# Peripherals.net
KiCad netlist of a schematic drawn in Altium Designer
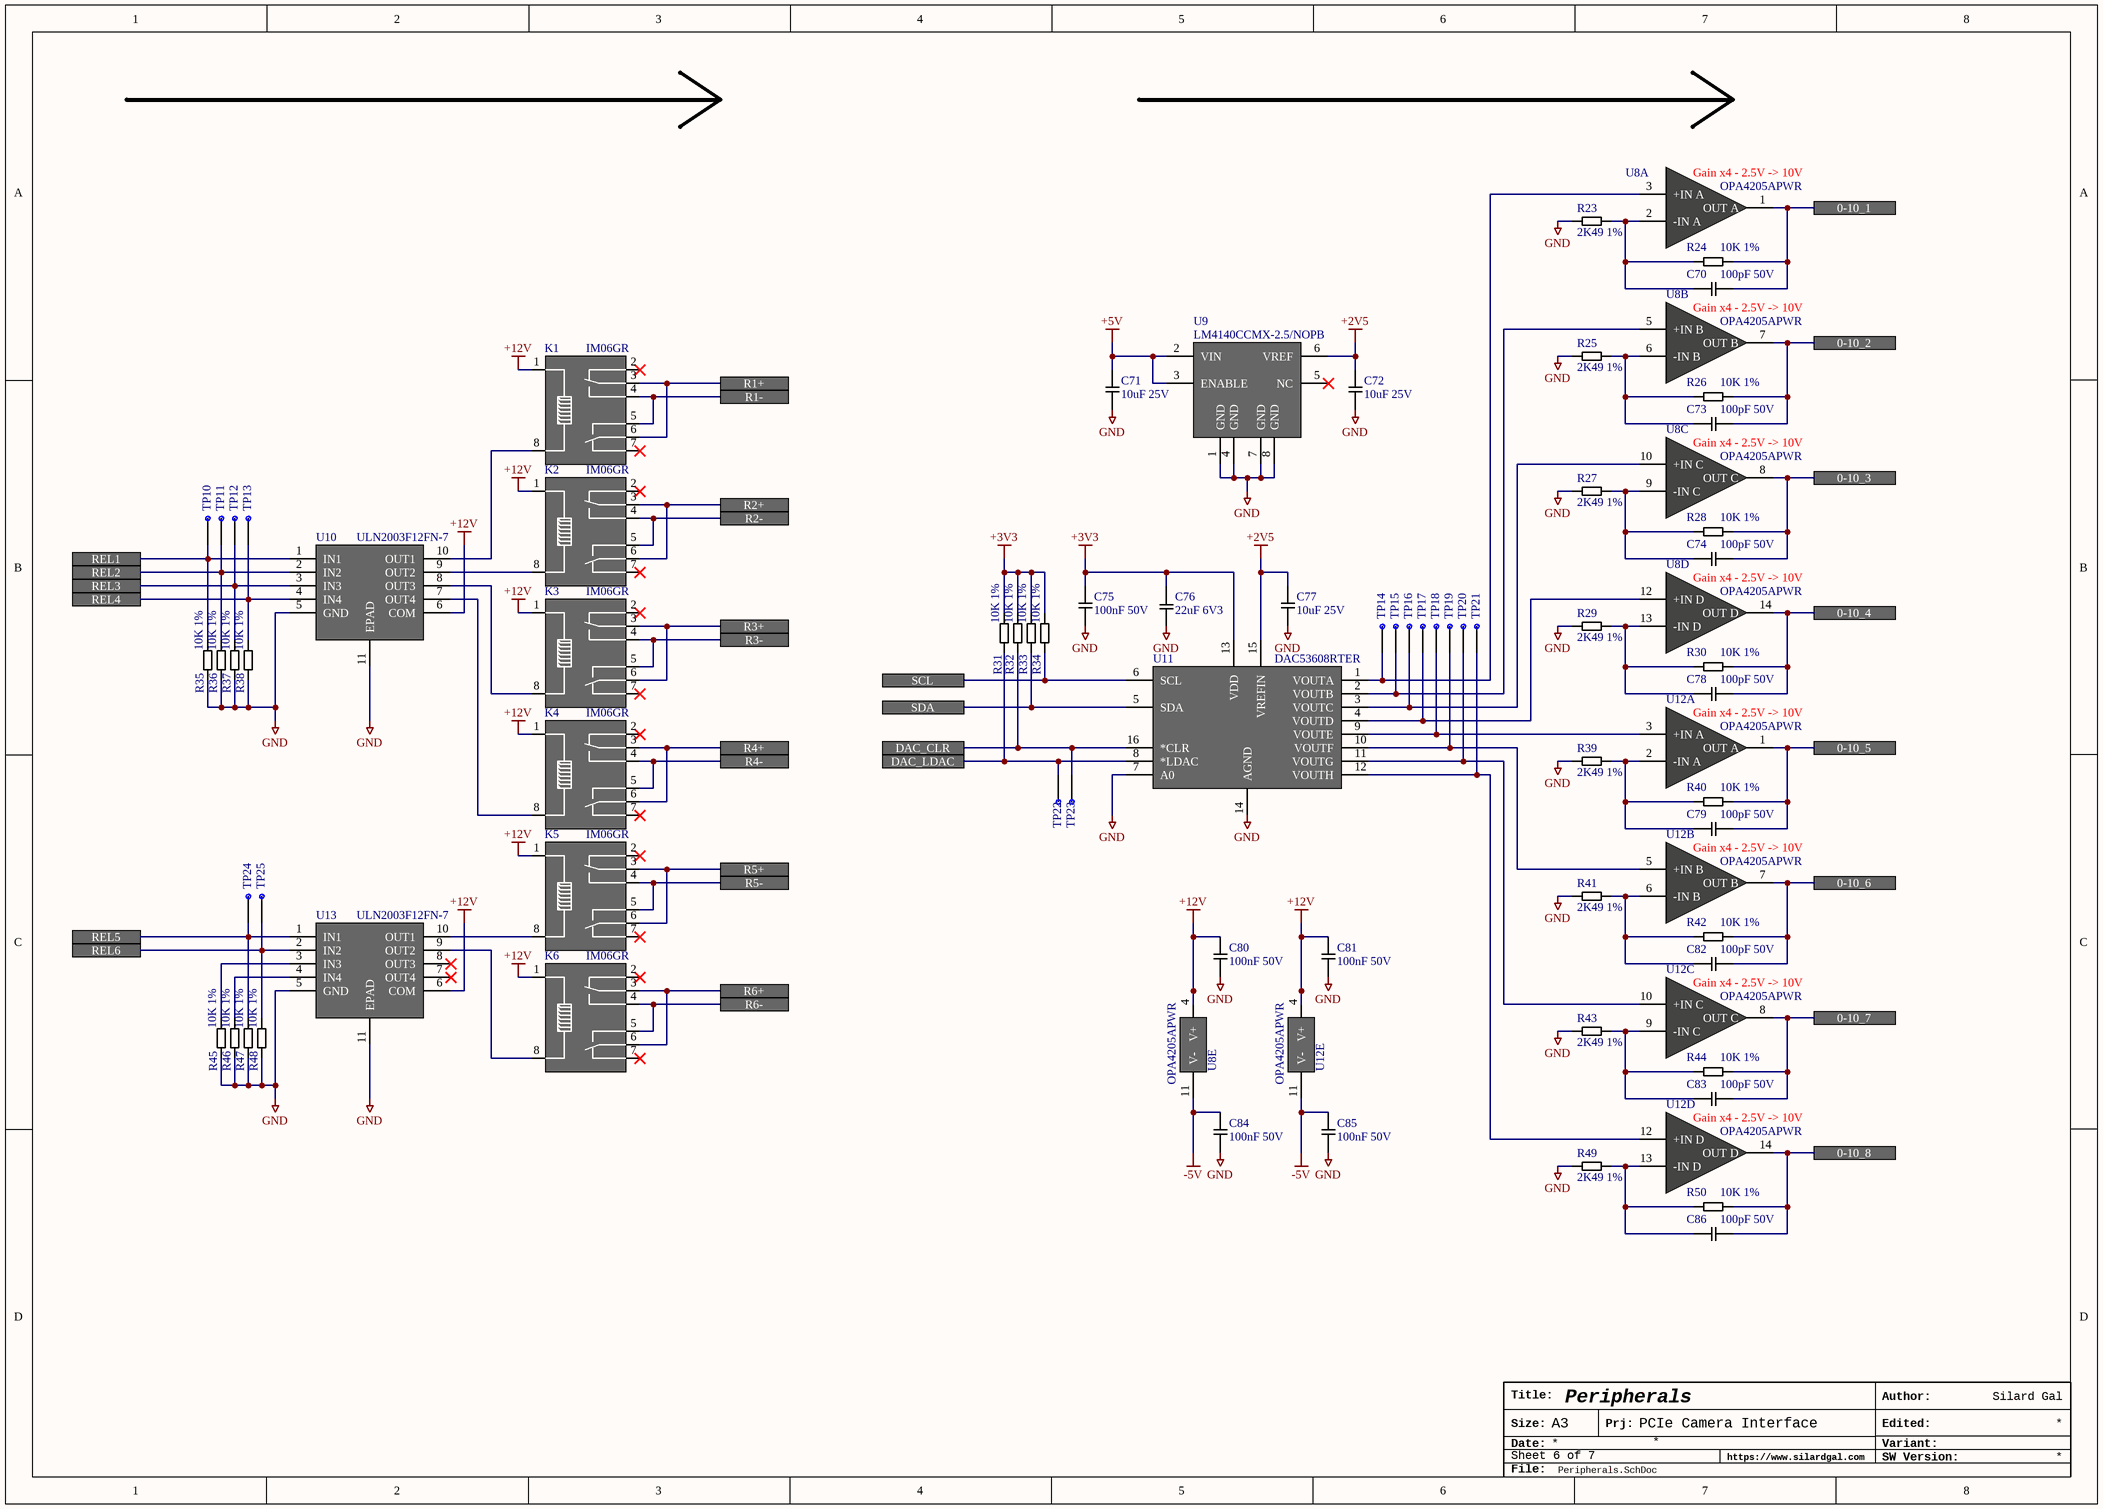
[diagram p0: Peripherals.SchDoc]

(export (version "E")
  (design (tool "Eeschema 10.0.6"))
  (components
    (comp (ref "C70")
      (value "100pF 50V")
      (footprint "CAPC1608X06N")
      (description "100 pF ±10% 50V Ceramic Capacitor C0G, NP0 0603 (1608 Metric)")
      (fields (field (name "MPN") "KGM15ACG1H101KT"))
      (libsource (lib "PCIe_Camera_Interface_Library") (part "100pF 50V"))
    )
    (comp (ref "C71")
      (value "10uF 25V")
      (footprint "CAPC1608X06N")
      (description "10 µF ±20% 25V Ceramic Capacitor X5R 0603 (1608 Metric)")
      (fields (field (name "MPN") "GRM188R61E106MA73D"))
      (libsource (lib "PCIe_Camera_Interface_Library") (part "10uF 25V"))
    )
    (comp (ref "C72")
      (value "10uF 25V")
      (footprint "CAPC1608X06N")
      (description "10 µF ±20% 25V Ceramic Capacitor X5R 0603 (1608 Metric)")
      (fields (field (name "MPN") "GRM188R61E106MA73D"))
      (libsource (lib "PCIe_Camera_Interface_Library") (part "10uF 25V"))
    )
    (comp (ref "C73")
      (value "100pF 50V")
      (footprint "CAPC1608X06N")
      (description "100 pF ±10% 50V Ceramic Capacitor C0G, NP0 0603 (1608 Metric)")
      (fields (field (name "MPN") "KGM15ACG1H101KT"))
      (libsource (lib "PCIe_Camera_Interface_Library") (part "100pF 50V"))
    )
    (comp (ref "C74")
      (value "100pF 50V")
      (footprint "CAPC1608X06N")
      (description "100 pF ±10% 50V Ceramic Capacitor C0G, NP0 0603 (1608 Metric)")
      (fields (field (name "MPN") "KGM15ACG1H101KT"))
      (libsource (lib "PCIe_Camera_Interface_Library") (part "100pF 50V"))
    )
    (comp (ref "C75")
      (value "100nF 50V")
      (footprint "CAPC1608X06N")
      (description "0.1 µF ±10% 50V Ceramic Capacitor X7R 0603 (1608 Metric)")
      (fields (field (name "MPN") "GCM188R71H104KA57D"))
      (libsource (lib "PCIe_Camera_Interface_Library") (part "100nF 50V"))
    )
    (comp (ref "C76")
      (value "22uF 6V3")
      (footprint "CAPC1608X06N")
      (description "22 µF ±20% 6.3V Ceramic Capacitor X5R 0603 (1608 Metric)")
      (fields (field (name "MPN") "GRM188R60J226MEA0D"))
      (libsource (lib "PCIe_Camera_Interface_Library") (part "22uF 6V3"))
    )
    (comp (ref "C77")
      (value "10uF 25V")
      (footprint "CAPC1608X06N")
      (description "10 µF ±20% 25V Ceramic Capacitor X5R 0603 (1608 Metric)")
      (fields (field (name "MPN") "GRM188R61E106MA73D"))
      (libsource (lib "PCIe_Camera_Interface_Library") (part "10uF 25V"))
    )
    (comp (ref "C78")
      (value "100pF 50V")
      (footprint "CAPC1608X06N")
      (description "100 pF ±10% 50V Ceramic Capacitor C0G, NP0 0603 (1608 Metric)")
      (fields (field (name "MPN") "KGM15ACG1H101KT"))
      (libsource (lib "PCIe_Camera_Interface_Library") (part "100pF 50V"))
    )
    (comp (ref "C79")
      (value "100pF 50V")
      (footprint "CAPC1608X06N")
      (description "100 pF ±10% 50V Ceramic Capacitor C0G, NP0 0603 (1608 Metric)")
      (fields (field (name "MPN") "KGM15ACG1H101KT"))
      (libsource (lib "PCIe_Camera_Interface_Library") (part "100pF 50V"))
    )
    (comp (ref "C80")
      (value "100nF 50V")
      (footprint "CAPC1608X06N")
      (description "0.1 µF ±10% 50V Ceramic Capacitor X7R 0603 (1608 Metric)")
      (fields (field (name "MPN") "GCM188R71H104KA57D"))
      (libsource (lib "PCIe_Camera_Interface_Library") (part "100nF 50V"))
    )
    (comp (ref "C81")
      (value "100nF 50V")
      (footprint "CAPC1608X06N")
      (description "0.1 µF ±10% 50V Ceramic Capacitor X7R 0603 (1608 Metric)")
      (fields (field (name "MPN") "GCM188R71H104KA57D"))
      (libsource (lib "PCIe_Camera_Interface_Library") (part "100nF 50V"))
    )
    (comp (ref "C82")
      (value "100pF 50V")
      (footprint "CAPC1608X06N")
      (description "100 pF ±10% 50V Ceramic Capacitor C0G, NP0 0603 (1608 Metric)")
      (fields (field (name "MPN") "KGM15ACG1H101KT"))
      (libsource (lib "PCIe_Camera_Interface_Library") (part "100pF 50V"))
    )
    (comp (ref "C83")
      (value "100pF 50V")
      (footprint "CAPC1608X06N")
      (description "100 pF ±10% 50V Ceramic Capacitor C0G, NP0 0603 (1608 Metric)")
      (fields (field (name "MPN") "KGM15ACG1H101KT"))
      (libsource (lib "PCIe_Camera_Interface_Library") (part "100pF 50V"))
    )
    (comp (ref "C84")
      (value "100nF 50V")
      (footprint "CAPC1608X06N")
      (description "0.1 µF ±10% 50V Ceramic Capacitor X7R 0603 (1608 Metric)")
      (fields (field (name "MPN") "GCM188R71H104KA57D"))
      (libsource (lib "PCIe_Camera_Interface_Library") (part "100nF 50V"))
    )
    (comp (ref "C85")
      (value "100nF 50V")
      (footprint "CAPC1608X06N")
      (description "0.1 µF ±10% 50V Ceramic Capacitor X7R 0603 (1608 Metric)")
      (fields (field (name "MPN") "GCM188R71H104KA57D"))
      (libsource (lib "PCIe_Camera_Interface_Library") (part "100nF 50V"))
    )
    (comp (ref "C86")
      (value "100pF 50V")
      (footprint "CAPC1608X06N")
      (description "100 pF ±10% 50V Ceramic Capacitor C0G, NP0 0603 (1608 Metric)")
      (fields (field (name "MPN") "KGM15ACG1H101KT"))
      (libsource (lib "PCIe_Camera_Interface_Library") (part "100pF 50V"))
    )
    (comp (ref "K1")
      (value "IM06GR")
      (footprint "IM06GR")
      (description "Telecom Relay DPDT (2 Form C) Surface Mount")
      (libsource (lib "PCIe_Camera_Interface_Library") (part "IM06GR"))
    )
    (comp (ref "K2")
      (value "IM06GR")
      (footprint "IM06GR")
      (description "Telecom Relay DPDT (2 Form C) Surface Mount")
      (libsource (lib "PCIe_Camera_Interface_Library") (part "IM06GR"))
    )
    (comp (ref "K3")
      (value "IM06GR")
      (footprint "IM06GR")
      (description "Telecom Relay DPDT (2 Form C) Surface Mount")
      (libsource (lib "PCIe_Camera_Interface_Library") (part "IM06GR"))
    )
    (comp (ref "K4")
      (value "IM06GR")
      (footprint "IM06GR")
      (description "Telecom Relay DPDT (2 Form C) Surface Mount")
      (libsource (lib "PCIe_Camera_Interface_Library") (part "IM06GR"))
    )
    (comp (ref "K5")
      (value "IM06GR")
      (footprint "IM06GR")
      (description "Telecom Relay DPDT (2 Form C) Surface Mount")
      (libsource (lib "PCIe_Camera_Interface_Library") (part "IM06GR"))
    )
    (comp (ref "K6")
      (value "IM06GR")
      (footprint "IM06GR")
      (description "Telecom Relay DPDT (2 Form C) Surface Mount")
      (libsource (lib "PCIe_Camera_Interface_Library") (part "IM06GR"))
    )
    (comp (ref "R23")
      (value "2K49 1%")
      (footprint "RESC1608X06N")
      (description "2.49 kOhms ±1% 0.1W, 1/10W Chip Resistor 0603 (1608 Metric) Automotive AEC-Q200 Thick Film")
      (fields (field (name "MPN") "RMCF0603FT2K49"))
      (libsource (lib "PCIe_Camera_Interface_Library") (part "2K49 1%"))
    )
    (comp (ref "R24")
      (value "10K 1%")
      (footprint "RESC1608X06N")
      (description "10 kOhms ±1% 0.1W, 1/10W Chip Resistor 0603 (1608 Metric) Automotive AEC-Q200 Thick Film")
      (fields (field (name "MPN") "ERJ-3EKF1002V"))
      (libsource (lib "PCIe_Camera_Interface_Library") (part "10K 1%"))
    )
    (comp (ref "R25")
      (value "2K49 1%")
      (footprint "RESC1608X06N")
      (description "2.49 kOhms ±1% 0.1W, 1/10W Chip Resistor 0603 (1608 Metric) Automotive AEC-Q200 Thick Film")
      (fields (field (name "MPN") "RMCF0603FT2K49"))
      (libsource (lib "PCIe_Camera_Interface_Library") (part "2K49 1%"))
    )
    (comp (ref "R26")
      (value "10K 1%")
      (footprint "RESC1608X06N")
      (description "10 kOhms ±1% 0.1W, 1/10W Chip Resistor 0603 (1608 Metric) Automotive AEC-Q200 Thick Film")
      (fields (field (name "MPN") "ERJ-3EKF1002V"))
      (libsource (lib "PCIe_Camera_Interface_Library") (part "10K 1%"))
    )
    (comp (ref "R27")
      (value "2K49 1%")
      (footprint "RESC1608X06N")
      (description "2.49 kOhms ±1% 0.1W, 1/10W Chip Resistor 0603 (1608 Metric) Automotive AEC-Q200 Thick Film")
      (fields (field (name "MPN") "RMCF0603FT2K49"))
      (libsource (lib "PCIe_Camera_Interface_Library") (part "2K49 1%"))
    )
    (comp (ref "R28")
      (value "10K 1%")
      (footprint "RESC1608X06N")
      (description "10 kOhms ±1% 0.1W, 1/10W Chip Resistor 0603 (1608 Metric) Automotive AEC-Q200 Thick Film")
      (fields (field (name "MPN") "ERJ-3EKF1002V"))
      (libsource (lib "PCIe_Camera_Interface_Library") (part "10K 1%"))
    )
    (comp (ref "R29")
      (value "2K49 1%")
      (footprint "RESC1608X06N")
      (description "2.49 kOhms ±1% 0.1W, 1/10W Chip Resistor 0603 (1608 Metric) Automotive AEC-Q200 Thick Film")
      (fields (field (name "MPN") "RMCF0603FT2K49"))
      (libsource (lib "PCIe_Camera_Interface_Library") (part "2K49 1%"))
    )
    (comp (ref "R30")
      (value "10K 1%")
      (footprint "RESC1608X06N")
      (description "10 kOhms ±1% 0.1W, 1/10W Chip Resistor 0603 (1608 Metric) Automotive AEC-Q200 Thick Film")
      (fields (field (name "MPN") "ERJ-3EKF1002V"))
      (libsource (lib "PCIe_Camera_Interface_Library") (part "10K 1%"))
    )
    (comp (ref "R31")
      (value "10K 1%")
      (footprint "RESC1608X06N")
      (description "10 kOhms ±1% 0.1W, 1/10W Chip Resistor 0603 (1608 Metric) Automotive AEC-Q200 Thick Film")
      (fields (field (name "MPN") "ERJ-3EKF1002V"))
      (libsource (lib "PCIe_Camera_Interface_Library") (part "10K 1%"))
    )
    (comp (ref "R32")
      (value "10K 1%")
      (footprint "RESC1608X06N")
      (description "10 kOhms ±1% 0.1W, 1/10W Chip Resistor 0603 (1608 Metric) Automotive AEC-Q200 Thick Film")
      (fields (field (name "MPN") "ERJ-3EKF1002V"))
      (libsource (lib "PCIe_Camera_Interface_Library") (part "10K 1%"))
    )
    (comp (ref "R33")
      (value "10K 1%")
      (footprint "RESC1608X06N")
      (description "10 kOhms ±1% 0.1W, 1/10W Chip Resistor 0603 (1608 Metric) Automotive AEC-Q200 Thick Film")
      (fields (field (name "MPN") "ERJ-3EKF1002V"))
      (libsource (lib "PCIe_Camera_Interface_Library") (part "10K 1%"))
    )
    (comp (ref "R34")
      (value "10K 1%")
      (footprint "RESC1608X06N")
      (description "10 kOhms ±1% 0.1W, 1/10W Chip Resistor 0603 (1608 Metric) Automotive AEC-Q200 Thick Film")
      (fields (field (name "MPN") "ERJ-3EKF1002V"))
      (libsource (lib "PCIe_Camera_Interface_Library") (part "10K 1%"))
    )
    (comp (ref "R35")
      (value "10K 1%")
      (footprint "RESC1608X06N")
      (description "10 kOhms ±1% 0.1W, 1/10W Chip Resistor 0603 (1608 Metric) Automotive AEC-Q200 Thick Film")
      (fields (field (name "MPN") "ERJ-3EKF1002V"))
      (libsource (lib "PCIe_Camera_Interface_Library") (part "10K 1%"))
    )
    (comp (ref "R36")
      (value "10K 1%")
      (footprint "RESC1608X06N")
      (description "10 kOhms ±1% 0.1W, 1/10W Chip Resistor 0603 (1608 Metric) Automotive AEC-Q200 Thick Film")
      (fields (field (name "MPN") "ERJ-3EKF1002V"))
      (libsource (lib "PCIe_Camera_Interface_Library") (part "10K 1%"))
    )
    (comp (ref "R37")
      (value "10K 1%")
      (footprint "RESC1608X06N")
      (description "10 kOhms ±1% 0.1W, 1/10W Chip Resistor 0603 (1608 Metric) Automotive AEC-Q200 Thick Film")
      (fields (field (name "MPN") "ERJ-3EKF1002V"))
      (libsource (lib "PCIe_Camera_Interface_Library") (part "10K 1%"))
    )
    (comp (ref "R38")
      (value "10K 1%")
      (footprint "RESC1608X06N")
      (description "10 kOhms ±1% 0.1W, 1/10W Chip Resistor 0603 (1608 Metric) Automotive AEC-Q200 Thick Film")
      (fields (field (name "MPN") "ERJ-3EKF1002V"))
      (libsource (lib "PCIe_Camera_Interface_Library") (part "10K 1%"))
    )
    (comp (ref "R39")
      (value "2K49 1%")
      (footprint "RESC1608X06N")
      (description "2.49 kOhms ±1% 0.1W, 1/10W Chip Resistor 0603 (1608 Metric) Automotive AEC-Q200 Thick Film")
      (fields (field (name "MPN") "RMCF0603FT2K49"))
      (libsource (lib "PCIe_Camera_Interface_Library") (part "2K49 1%"))
    )
    (comp (ref "R40")
      (value "10K 1%")
      (footprint "RESC1608X06N")
      (description "10 kOhms ±1% 0.1W, 1/10W Chip Resistor 0603 (1608 Metric) Automotive AEC-Q200 Thick Film")
      (fields (field (name "MPN") "ERJ-3EKF1002V"))
      (libsource (lib "PCIe_Camera_Interface_Library") (part "10K 1%"))
    )
    (comp (ref "R41")
      (value "2K49 1%")
      (footprint "RESC1608X06N")
      (description "2.49 kOhms ±1% 0.1W, 1/10W Chip Resistor 0603 (1608 Metric) Automotive AEC-Q200 Thick Film")
      (fields (field (name "MPN") "RMCF0603FT2K49"))
      (libsource (lib "PCIe_Camera_Interface_Library") (part "2K49 1%"))
    )
    (comp (ref "R42")
      (value "10K 1%")
      (footprint "RESC1608X06N")
      (description "10 kOhms ±1% 0.1W, 1/10W Chip Resistor 0603 (1608 Metric) Automotive AEC-Q200 Thick Film")
      (fields (field (name "MPN") "ERJ-3EKF1002V"))
      (libsource (lib "PCIe_Camera_Interface_Library") (part "10K 1%"))
    )
    (comp (ref "R43")
      (value "2K49 1%")
      (footprint "RESC1608X06N")
      (description "2.49 kOhms ±1% 0.1W, 1/10W Chip Resistor 0603 (1608 Metric) Automotive AEC-Q200 Thick Film")
      (fields (field (name "MPN") "RMCF0603FT2K49"))
      (libsource (lib "PCIe_Camera_Interface_Library") (part "2K49 1%"))
    )
    (comp (ref "R44")
      (value "10K 1%")
      (footprint "RESC1608X06N")
      (description "10 kOhms ±1% 0.1W, 1/10W Chip Resistor 0603 (1608 Metric) Automotive AEC-Q200 Thick Film")
      (fields (field (name "MPN") "ERJ-3EKF1002V"))
      (libsource (lib "PCIe_Camera_Interface_Library") (part "10K 1%"))
    )
    (comp (ref "R45")
      (value "10K 1%")
      (footprint "RESC1608X06N")
      (description "10 kOhms ±1% 0.1W, 1/10W Chip Resistor 0603 (1608 Metric) Automotive AEC-Q200 Thick Film")
      (fields (field (name "MPN") "ERJ-3EKF1002V"))
      (libsource (lib "PCIe_Camera_Interface_Library") (part "10K 1%"))
    )
    (comp (ref "R46")
      (value "10K 1%")
      (footprint "RESC1608X06N")
      (description "10 kOhms ±1% 0.1W, 1/10W Chip Resistor 0603 (1608 Metric) Automotive AEC-Q200 Thick Film")
      (fields (field (name "MPN") "ERJ-3EKF1002V"))
      (libsource (lib "PCIe_Camera_Interface_Library") (part "10K 1%"))
    )
    (comp (ref "R47")
      (value "10K 1%")
      (footprint "RESC1608X06N")
      (description "10 kOhms ±1% 0.1W, 1/10W Chip Resistor 0603 (1608 Metric) Automotive AEC-Q200 Thick Film")
      (fields (field (name "MPN") "ERJ-3EKF1002V"))
      (libsource (lib "PCIe_Camera_Interface_Library") (part "10K 1%"))
    )
    (comp (ref "R48")
      (value "10K 1%")
      (footprint "RESC1608X06N")
      (description "10 kOhms ±1% 0.1W, 1/10W Chip Resistor 0603 (1608 Metric) Automotive AEC-Q200 Thick Film")
      (fields (field (name "MPN") "ERJ-3EKF1002V"))
      (libsource (lib "PCIe_Camera_Interface_Library") (part "10K 1%"))
    )
    (comp (ref "R49")
      (value "2K49 1%")
      (footprint "RESC1608X06N")
      (description "2.49 kOhms ±1% 0.1W, 1/10W Chip Resistor 0603 (1608 Metric) Automotive AEC-Q200 Thick Film")
      (fields (field (name "MPN") "RMCF0603FT2K49"))
      (libsource (lib "PCIe_Camera_Interface_Library") (part "2K49 1%"))
    )
    (comp (ref "R50")
      (value "10K 1%")
      (footprint "RESC1608X06N")
      (description "10 kOhms ±1% 0.1W, 1/10W Chip Resistor 0603 (1608 Metric) Automotive AEC-Q200 Thick Film")
      (fields (field (name "MPN") "ERJ-3EKF1002V"))
      (libsource (lib "PCIe_Camera_Interface_Library") (part "10K 1%"))
    )
    (comp (ref "TP10")
      (value "TP")
      (footprint "TP")
      (libsource (lib "PCIe_Camera_Interface_Library") (part "TP"))
    )
    (comp (ref "TP11")
      (value "TP")
      (footprint "TP")
      (libsource (lib "PCIe_Camera_Interface_Library") (part "TP"))
    )
    (comp (ref "TP12")
      (value "TP")
      (footprint "TP")
      (libsource (lib "PCIe_Camera_Interface_Library") (part "TP"))
    )
    (comp (ref "TP13")
      (value "TP")
      (footprint "TP")
      (libsource (lib "PCIe_Camera_Interface_Library") (part "TP"))
    )
    (comp (ref "TP14")
      (value "TP")
      (footprint "TP")
      (libsource (lib "PCIe_Camera_Interface_Library") (part "TP"))
    )
    (comp (ref "TP15")
      (value "TP")
      (footprint "TP")
      (libsource (lib "PCIe_Camera_Interface_Library") (part "TP"))
    )
    (comp (ref "TP16")
      (value "TP")
      (footprint "TP")
      (libsource (lib "PCIe_Camera_Interface_Library") (part "TP"))
    )
    (comp (ref "TP17")
      (value "TP")
      (footprint "TP")
      (libsource (lib "PCIe_Camera_Interface_Library") (part "TP"))
    )
    (comp (ref "TP18")
      (value "TP")
      (footprint "TP")
      (libsource (lib "PCIe_Camera_Interface_Library") (part "TP"))
    )
    (comp (ref "TP19")
      (value "TP")
      (footprint "TP")
      (libsource (lib "PCIe_Camera_Interface_Library") (part "TP"))
    )
    (comp (ref "TP20")
      (value "TP")
      (footprint "TP")
      (libsource (lib "PCIe_Camera_Interface_Library") (part "TP"))
    )
    (comp (ref "TP21")
      (value "TP")
      (footprint "TP")
      (libsource (lib "PCIe_Camera_Interface_Library") (part "TP"))
    )
    (comp (ref "TP22")
      (value "TP")
      (footprint "TP")
      (libsource (lib "PCIe_Camera_Interface_Library") (part "TP"))
    )
    (comp (ref "TP23")
      (value "TP")
      (footprint "TP")
      (libsource (lib "PCIe_Camera_Interface_Library") (part "TP"))
    )
    (comp (ref "TP24")
      (value "TP")
      (footprint "TP")
      (libsource (lib "PCIe_Camera_Interface_Library") (part "TP"))
    )
    (comp (ref "TP25")
      (value "TP")
      (footprint "TP")
      (libsource (lib "PCIe_Camera_Interface_Library") (part "TP"))
    )
    (comp (ref "U8")
      (value "OPA4205APWR")
      (footprint "TSSO14P440")
      (description "General Purpose Amplifier 4 Circuit Push-Pull, Rail-to-Rail 14-TSSOP")
      (libsource (lib "PCIe_Camera_Interface_Library") (part "OPA4205APWR"))
    )
    (comp (ref "U9")
      (value "LM4140CCMX-2.5/NOPB")
      (footprint "SOIC127P599X175-8N")
      (description "Series Voltage Reference IC Fixed 2.5V V ±0.1% 8 mA 8-SOIC")
      (libsource (lib "PCIe_Camera_Interface_Library") (part "LM4140CCMX-2.5/NOPB"))
    )
    (comp (ref "U10")
      (value "ULN2003F12FN-7")
      (footprint "DFN3030")
      (description "Power Switch/Driver 1:1 Darlington 700mA U-DFN3030-10")
      (libsource (lib "PCIe_Camera_Interface_Library") (part "ULN2003F12FN-7"))
    )
    (comp (ref "U11")
      (value "DAC53608RTER")
      (footprint "QFN16P300X300")
      (description "10 Bit Digital to Analog Converter 8 16-WQFN (3x3)")
      (libsource (lib "PCIe_Camera_Interface_Library") (part "DAC53608RTER"))
    )
    (comp (ref "U12")
      (value "OPA4205APWR")
      (footprint "TSSO14P440")
      (description "General Purpose Amplifier 4 Circuit Push-Pull, Rail-to-Rail 14-TSSOP")
      (libsource (lib "PCIe_Camera_Interface_Library") (part "OPA4205APWR"))
    )
    (comp (ref "U13")
      (value "ULN2003F12FN-7")
      (footprint "DFN3030")
      (description "Power Switch/Driver 1:1 Darlington 700mA U-DFN3030-10")
      (libsource (lib "PCIe_Camera_Interface_Library") (part "ULN2003F12FN-7"))
    )
  )
  (nets
    (net (code "1") (name "+2V5") (class "Default")
      (node (ref "C72") (pin "2") (pinfunction "2_2") (pintype "passive"))
      (node (ref "C77") (pin "2") (pinfunction "2_2") (pintype "passive"))
      (node (ref "U11") (pin "15") (pinfunction "VREFIN_15") (pintype "passive"))
      (node (ref "U9") (pin "6") (pinfunction "VREF_6") (pintype "passive"))
    )
    (net (code "2") (name "+3V3") (class "Default")
      (node (ref "C75") (pin "2") (pinfunction "2_2") (pintype "passive"))
      (node (ref "C76") (pin "1") (pinfunction "1_1") (pintype "passive"))
      (node (ref "R31") (pin "1") (pinfunction "1_1") (pintype "passive"))
      (node (ref "R32") (pin "1") (pinfunction "1_1") (pintype "passive"))
      (node (ref "R33") (pin "1") (pinfunction "1_1") (pintype "passive"))
      (node (ref "R34") (pin "1") (pinfunction "1_1") (pintype "passive"))
      (node (ref "U11") (pin "13") (pinfunction "VDD_13") (pintype "passive"))
    )
    (net (code "3") (name "+5V") (class "Default")
      (node (ref "C71") (pin "2") (pinfunction "2_2") (pintype "passive"))
      (node (ref "U9") (pin "2") (pinfunction "VIN_2") (pintype "passive"))
      (node (ref "U9") (pin "3") (pinfunction "ENABLE_3") (pintype "passive"))
    )
    (net (code "4") (name "+12V") (class "Default")
      (node (ref "C80") (pin "2") (pinfunction "2_2") (pintype "passive"))
      (node (ref "C81") (pin "2") (pinfunction "2_2") (pintype "passive"))
      (node (ref "K1") (pin "1") (pinfunction "1_1") (pintype "passive"))
      (node (ref "K2") (pin "1") (pinfunction "1_1") (pintype "passive"))
      (node (ref "K3") (pin "1") (pinfunction "1_1") (pintype "passive"))
      (node (ref "K4") (pin "1") (pinfunction "1_1") (pintype "passive"))
      (node (ref "K5") (pin "1") (pinfunction "1_1") (pintype "passive"))
      (node (ref "K6") (pin "1") (pinfunction "1_1") (pintype "passive"))
      (node (ref "U10") (pin "6") (pinfunction "COM_6") (pintype "passive"))
      (node (ref "U12") (pin "4") (pinfunction "V+_4") (pintype "power_in"))
      (node (ref "U13") (pin "6") (pinfunction "COM_6") (pintype "passive"))
      (node (ref "U8") (pin "4") (pinfunction "V+_4") (pintype "power_in"))
    )
    (net (code "5") (name "-5V") (class "Default")
      (node (ref "C84") (pin "2") (pinfunction "2_2") (pintype "passive"))
      (node (ref "C85") (pin "2") (pinfunction "2_2") (pintype "passive"))
      (node (ref "U12") (pin "11") (pinfunction "V-_11") (pintype "power_in"))
      (node (ref "U8") (pin "11") (pinfunction "V-_11") (pintype "power_in"))
    )
    (net (code "6") (name "/0-10_1") (class "Default")
      (node (ref "C70") (pin "2") (pinfunction "2_2") (pintype "passive"))
      (node (ref "R24") (pin "2") (pinfunction "2_2") (pintype "passive"))
      (node (ref "U8") (pin "1") (pinfunction "OUT_A_1") (pintype "passive"))
    )
    (net (code "7") (name "/0-10_2") (class "Default")
      (node (ref "C73") (pin "2") (pinfunction "2_2") (pintype "passive"))
      (node (ref "R26") (pin "2") (pinfunction "2_2") (pintype "passive"))
      (node (ref "U8") (pin "7") (pinfunction "OUT_B_7") (pintype "passive"))
    )
    (net (code "8") (name "/0-10_3") (class "Default")
      (node (ref "C74") (pin "2") (pinfunction "2_2") (pintype "passive"))
      (node (ref "R28") (pin "2") (pinfunction "2_2") (pintype "passive"))
      (node (ref "U8") (pin "8") (pinfunction "OUT_C_8") (pintype "passive"))
    )
    (net (code "9") (name "/0-10_4") (class "Default")
      (node (ref "C78") (pin "2") (pinfunction "2_2") (pintype "passive"))
      (node (ref "R30") (pin "2") (pinfunction "2_2") (pintype "passive"))
      (node (ref "U8") (pin "14") (pinfunction "OUT_D_14") (pintype "passive"))
    )
    (net (code "10") (name "/0-10_5") (class "Default")
      (node (ref "C79") (pin "2") (pinfunction "2_2") (pintype "passive"))
      (node (ref "R40") (pin "2") (pinfunction "2_2") (pintype "passive"))
      (node (ref "U12") (pin "1") (pinfunction "OUT_A_1") (pintype "passive"))
    )
    (net (code "11") (name "/0-10_6") (class "Default")
      (node (ref "C82") (pin "2") (pinfunction "2_2") (pintype "passive"))
      (node (ref "R42") (pin "2") (pinfunction "2_2") (pintype "passive"))
      (node (ref "U12") (pin "7") (pinfunction "OUT_B_7") (pintype "passive"))
    )
    (net (code "12") (name "/0-10_7") (class "Default")
      (node (ref "C83") (pin "2") (pinfunction "2_2") (pintype "passive"))
      (node (ref "R44") (pin "2") (pinfunction "2_2") (pintype "passive"))
      (node (ref "U12") (pin "8") (pinfunction "OUT_C_8") (pintype "passive"))
    )
    (net (code "13") (name "/0-10_8") (class "Default")
      (node (ref "C86") (pin "2") (pinfunction "2_2") (pintype "passive"))
      (node (ref "R50") (pin "2") (pinfunction "2_2") (pintype "passive"))
      (node (ref "U12") (pin "14") (pinfunction "OUT_D_14") (pintype "passive"))
    )
    (net (code "14") (name "/DAC_CLR") (class "Default")
      (node (ref "R32") (pin "2") (pinfunction "2_2") (pintype "passive"))
      (node (ref "TP23") (pin "1") (pinfunction "1_1") (pintype "passive"))
      (node (ref "U11") (pin "16") (pinfunction "*CLR_16") (pintype "passive"))
    )
    (net (code "15") (name "/DAC_LDAC") (class "Default")
      (node (ref "R31") (pin "2") (pinfunction "2_2") (pintype "passive"))
      (node (ref "TP22") (pin "1") (pinfunction "1_1") (pintype "passive"))
      (node (ref "U11") (pin "8") (pinfunction "*LDAC_8") (pintype "passive"))
    )
    (net (code "16") (name "/R1+") (class "Default")
      (node (ref "K1") (pin "3") (pinfunction "3_3") (pintype "passive"))
      (node (ref "K1") (pin "6") (pinfunction "6_6") (pintype "passive"))
    )
    (net (code "17") (name "/R1-") (class "Default")
      (node (ref "K1") (pin "4") (pinfunction "4_4") (pintype "passive"))
      (node (ref "K1") (pin "5") (pinfunction "5_5") (pintype "passive"))
    )
    (net (code "18") (name "/R2+") (class "Default")
      (node (ref "K2") (pin "3") (pinfunction "3_3") (pintype "passive"))
      (node (ref "K2") (pin "6") (pinfunction "6_6") (pintype "passive"))
    )
    (net (code "19") (name "/R2-") (class "Default")
      (node (ref "K2") (pin "4") (pinfunction "4_4") (pintype "passive"))
      (node (ref "K2") (pin "5") (pinfunction "5_5") (pintype "passive"))
    )
    (net (code "20") (name "/R3+") (class "Default")
      (node (ref "K3") (pin "3") (pinfunction "3_3") (pintype "passive"))
      (node (ref "K3") (pin "6") (pinfunction "6_6") (pintype "passive"))
    )
    (net (code "21") (name "/R3-") (class "Default")
      (node (ref "K3") (pin "4") (pinfunction "4_4") (pintype "passive"))
      (node (ref "K3") (pin "5") (pinfunction "5_5") (pintype "passive"))
    )
    (net (code "22") (name "/R4+") (class "Default")
      (node (ref "K4") (pin "3") (pinfunction "3_3") (pintype "passive"))
      (node (ref "K4") (pin "6") (pinfunction "6_6") (pintype "passive"))
    )
    (net (code "23") (name "/R4-") (class "Default")
      (node (ref "K4") (pin "4") (pinfunction "4_4") (pintype "passive"))
      (node (ref "K4") (pin "5") (pinfunction "5_5") (pintype "passive"))
    )
    (net (code "24") (name "/R5+") (class "Default")
      (node (ref "K5") (pin "3") (pinfunction "3_3") (pintype "passive"))
      (node (ref "K5") (pin "6") (pinfunction "6_6") (pintype "passive"))
    )
    (net (code "25") (name "/R5-") (class "Default")
      (node (ref "K5") (pin "4") (pinfunction "4_4") (pintype "passive"))
      (node (ref "K5") (pin "5") (pinfunction "5_5") (pintype "passive"))
    )
    (net (code "26") (name "/R6+") (class "Default")
      (node (ref "K6") (pin "3") (pinfunction "3_3") (pintype "passive"))
      (node (ref "K6") (pin "6") (pinfunction "6_6") (pintype "passive"))
    )
    (net (code "27") (name "/R6-") (class "Default")
      (node (ref "K6") (pin "4") (pinfunction "4_4") (pintype "passive"))
      (node (ref "K6") (pin "5") (pinfunction "5_5") (pintype "passive"))
    )
    (net (code "28") (name "/REL1") (class "Default")
      (node (ref "R35") (pin "1") (pinfunction "1_1") (pintype "passive"))
      (node (ref "TP10") (pin "1") (pinfunction "1_1") (pintype "passive"))
      (node (ref "U10") (pin "1") (pinfunction "IN1_1") (pintype "passive"))
    )
    (net (code "29") (name "/REL2") (class "Default")
      (node (ref "R36") (pin "1") (pinfunction "1_1") (pintype "passive"))
      (node (ref "TP11") (pin "1") (pinfunction "1_1") (pintype "passive"))
      (node (ref "U10") (pin "2") (pinfunction "IN2_2") (pintype "passive"))
    )
    (net (code "30") (name "/REL3") (class "Default")
      (node (ref "R37") (pin "1") (pinfunction "1_1") (pintype "passive"))
      (node (ref "TP12") (pin "1") (pinfunction "1_1") (pintype "passive"))
      (node (ref "U10") (pin "3") (pinfunction "IN3_3") (pintype "passive"))
    )
    (net (code "31") (name "/REL4") (class "Default")
      (node (ref "R38") (pin "1") (pinfunction "1_1") (pintype "passive"))
      (node (ref "TP13") (pin "1") (pinfunction "1_1") (pintype "passive"))
      (node (ref "U10") (pin "4") (pinfunction "IN4_4") (pintype "passive"))
    )
    (net (code "32") (name "/REL5") (class "Default")
      (node (ref "R47") (pin "1") (pinfunction "1_1") (pintype "passive"))
      (node (ref "TP24") (pin "1") (pinfunction "1_1") (pintype "passive"))
      (node (ref "U13") (pin "1") (pinfunction "IN1_1") (pintype "passive"))
    )
    (net (code "33") (name "/REL6") (class "Default")
      (node (ref "R48") (pin "1") (pinfunction "1_1") (pintype "passive"))
      (node (ref "TP25") (pin "1") (pinfunction "1_1") (pintype "passive"))
      (node (ref "U13") (pin "2") (pinfunction "IN2_2") (pintype "passive"))
    )
    (net (code "34") (name "/SCL") (class "Default")
      (node (ref "R34") (pin "2") (pinfunction "2_2") (pintype "passive"))
      (node (ref "U11") (pin "6") (pinfunction "SCL_6") (pintype "passive"))
    )
    (net (code "35") (name "/SDA") (class "Default")
      (node (ref "R33") (pin "2") (pinfunction "2_2") (pintype "passive"))
      (node (ref "U11") (pin "5") (pinfunction "SDA_5") (pintype "passive"))
    )
    (net (code "36") (name "GND") (class "Default")
      (node (ref "C71") (pin "1") (pinfunction "1_1") (pintype "passive"))
      (node (ref "C72") (pin "1") (pinfunction "1_1") (pintype "passive"))
      (node (ref "C75") (pin "1") (pinfunction "1_1") (pintype "passive"))
      (node (ref "C76") (pin "2") (pinfunction "2_2") (pintype "passive"))
      (node (ref "C77") (pin "1") (pinfunction "1_1") (pintype "passive"))
      (node (ref "C80") (pin "1") (pinfunction "1_1") (pintype "passive"))
      (node (ref "C81") (pin "1") (pinfunction "1_1") (pintype "passive"))
      (node (ref "C84") (pin "1") (pinfunction "1_1") (pintype "passive"))
      (node (ref "C85") (pin "1") (pinfunction "1_1") (pintype "passive"))
      (node (ref "R23") (pin "1") (pinfunction "1_1") (pintype "passive"))
      (node (ref "R25") (pin "1") (pinfunction "1_1") (pintype "passive"))
      (node (ref "R27") (pin "1") (pinfunction "1_1") (pintype "passive"))
      (node (ref "R29") (pin "1") (pinfunction "1_1") (pintype "passive"))
      (node (ref "R35") (pin "2") (pinfunction "2_2") (pintype "passive"))
      (node (ref "R36") (pin "2") (pinfunction "2_2") (pintype "passive"))
      (node (ref "R37") (pin "2") (pinfunction "2_2") (pintype "passive"))
      (node (ref "R38") (pin "2") (pinfunction "2_2") (pintype "passive"))
      (node (ref "R39") (pin "1") (pinfunction "1_1") (pintype "passive"))
      (node (ref "R41") (pin "1") (pinfunction "1_1") (pintype "passive"))
      (node (ref "R43") (pin "1") (pinfunction "1_1") (pintype "passive"))
      (node (ref "R45") (pin "2") (pinfunction "2_2") (pintype "passive"))
      (node (ref "R46") (pin "2") (pinfunction "2_2") (pintype "passive"))
      (node (ref "R47") (pin "2") (pinfunction "2_2") (pintype "passive"))
      (node (ref "R48") (pin "2") (pinfunction "2_2") (pintype "passive"))
      (node (ref "R49") (pin "1") (pinfunction "1_1") (pintype "passive"))
      (node (ref "U10") (pin "11") (pinfunction "EPAD_11") (pintype "passive"))
      (node (ref "U10") (pin "5") (pinfunction "GND_5") (pintype "passive"))
      (node (ref "U11") (pin "14") (pinfunction "AGND_14") (pintype "passive"))
      (node (ref "U11") (pin "7") (pinfunction "A0_7") (pintype "passive"))
      (node (ref "U13") (pin "11") (pinfunction "EPAD_11") (pintype "passive"))
      (node (ref "U13") (pin "5") (pinfunction "GND_5") (pintype "passive"))
      (node (ref "U9") (pin "1") (pinfunction "GND_1") (pintype "passive"))
      (node (ref "U9") (pin "4") (pinfunction "GND_4") (pintype "passive"))
      (node (ref "U9") (pin "7") (pinfunction "GND_7") (pintype "passive"))
      (node (ref "U9") (pin "8") (pinfunction "GND_8") (pintype "passive"))
    )
    (net (code "37") (name "Net-(U8A--IN_A)") (class "Default")
      (node (ref "C70") (pin "1") (pinfunction "1_1") (pintype "passive"))
      (node (ref "R23") (pin "2") (pinfunction "2_2") (pintype "passive"))
      (node (ref "R24") (pin "1") (pinfunction "1_1") (pintype "passive"))
      (node (ref "U8") (pin "2") (pinfunction "-IN_A_2") (pintype "passive"))
    )
    (net (code "38") (name "Net-(U8B--IN_B)") (class "Default")
      (node (ref "C73") (pin "1") (pinfunction "1_1") (pintype "passive"))
      (node (ref "R25") (pin "2") (pinfunction "2_2") (pintype "passive"))
      (node (ref "R26") (pin "1") (pinfunction "1_1") (pintype "passive"))
      (node (ref "U8") (pin "6") (pinfunction "-IN_B_6") (pintype "passive"))
    )
    (net (code "39") (name "Net-(U8C--IN_C)") (class "Default")
      (node (ref "C74") (pin "1") (pinfunction "1_1") (pintype "passive"))
      (node (ref "R27") (pin "2") (pinfunction "2_2") (pintype "passive"))
      (node (ref "R28") (pin "1") (pinfunction "1_1") (pintype "passive"))
      (node (ref "U8") (pin "9") (pinfunction "-IN_C_9") (pintype "passive"))
    )
    (net (code "40") (name "Net-(U8D--IN_D)") (class "Default")
      (node (ref "C78") (pin "1") (pinfunction "1_1") (pintype "passive"))
      (node (ref "R29") (pin "2") (pinfunction "2_2") (pintype "passive"))
      (node (ref "R30") (pin "1") (pinfunction "1_1") (pintype "passive"))
      (node (ref "U8") (pin "13") (pinfunction "-IN_D_13") (pintype "passive"))
    )
    (net (code "41") (name "Net-(U10-OUT1)") (class "Default")
      (node (ref "K1") (pin "8") (pinfunction "8_8") (pintype "passive"))
      (node (ref "U10") (pin "10") (pinfunction "OUT1_10") (pintype "passive"))
    )
    (net (code "42") (name "Net-(U10-OUT2)") (class "Default")
      (node (ref "K2") (pin "8") (pinfunction "8_8") (pintype "passive"))
      (node (ref "U10") (pin "9") (pinfunction "OUT2_9") (pintype "passive"))
    )
    (net (code "43") (name "Net-(U10-OUT3)") (class "Default")
      (node (ref "K3") (pin "8") (pinfunction "8_8") (pintype "passive"))
      (node (ref "U10") (pin "8") (pinfunction "OUT3_8") (pintype "passive"))
    )
    (net (code "44") (name "Net-(U10-OUT4)") (class "Default")
      (node (ref "K4") (pin "8") (pinfunction "8_8") (pintype "passive"))
      (node (ref "U10") (pin "7") (pinfunction "OUT4_7") (pintype "passive"))
    )
    (net (code "45") (name "Net-(U11-VOUTA)") (class "Default")
      (node (ref "TP14") (pin "1") (pinfunction "1_1") (pintype "passive"))
      (node (ref "U11") (pin "1") (pinfunction "VOUTA_1") (pintype "passive"))
      (node (ref "U8") (pin "3") (pinfunction "+IN_A_3") (pintype "passive"))
    )
    (net (code "46") (name "Net-(U11-VOUTB)") (class "Default")
      (node (ref "TP15") (pin "1") (pinfunction "1_1") (pintype "passive"))
      (node (ref "U11") (pin "2") (pinfunction "VOUTB_2") (pintype "passive"))
      (node (ref "U8") (pin "5") (pinfunction "+IN_B_5") (pintype "passive"))
    )
    (net (code "47") (name "Net-(U11-VOUTC)") (class "Default")
      (node (ref "TP16") (pin "1") (pinfunction "1_1") (pintype "passive"))
      (node (ref "U11") (pin "3") (pinfunction "VOUTC_3") (pintype "passive"))
      (node (ref "U8") (pin "10") (pinfunction "+IN_C_10") (pintype "passive"))
    )
    (net (code "48") (name "Net-(U11-VOUTD)") (class "Default")
      (node (ref "TP17") (pin "1") (pinfunction "1_1") (pintype "passive"))
      (node (ref "U11") (pin "4") (pinfunction "VOUTD_4") (pintype "passive"))
      (node (ref "U8") (pin "12") (pinfunction "+IN_D_12") (pintype "passive"))
    )
    (net (code "49") (name "Net-(U11-VOUTE)") (class "Default")
      (node (ref "TP18") (pin "1") (pinfunction "1_1") (pintype "passive"))
      (node (ref "U11") (pin "9") (pinfunction "VOUTE_9") (pintype "passive"))
      (node (ref "U12") (pin "3") (pinfunction "+IN_A_3") (pintype "passive"))
    )
    (net (code "50") (name "Net-(U11-VOUTF)") (class "Default")
      (node (ref "TP19") (pin "1") (pinfunction "1_1") (pintype "passive"))
      (node (ref "U11") (pin "10") (pinfunction "VOUTF_10") (pintype "passive"))
      (node (ref "U12") (pin "5") (pinfunction "+IN_B_5") (pintype "passive"))
    )
    (net (code "51") (name "Net-(U11-VOUTG)") (class "Default")
      (node (ref "TP20") (pin "1") (pinfunction "1_1") (pintype "passive"))
      (node (ref "U11") (pin "11") (pinfunction "VOUTG_11") (pintype "passive"))
      (node (ref "U12") (pin "10") (pinfunction "+IN_C_10") (pintype "passive"))
    )
    (net (code "52") (name "Net-(U11-VOUTH)") (class "Default")
      (node (ref "TP21") (pin "1") (pinfunction "1_1") (pintype "passive"))
      (node (ref "U11") (pin "12") (pinfunction "VOUTH_12") (pintype "passive"))
      (node (ref "U12") (pin "12") (pinfunction "+IN_D_12") (pintype "passive"))
    )
    (net (code "53") (name "Net-(U12A--IN_A)") (class "Default")
      (node (ref "C79") (pin "1") (pinfunction "1_1") (pintype "passive"))
      (node (ref "R39") (pin "2") (pinfunction "2_2") (pintype "passive"))
      (node (ref "R40") (pin "1") (pinfunction "1_1") (pintype "passive"))
      (node (ref "U12") (pin "2") (pinfunction "-IN_A_2") (pintype "passive"))
    )
    (net (code "54") (name "Net-(U12B--IN_B)") (class "Default")
      (node (ref "C82") (pin "1") (pinfunction "1_1") (pintype "passive"))
      (node (ref "R41") (pin "2") (pinfunction "2_2") (pintype "passive"))
      (node (ref "R42") (pin "1") (pinfunction "1_1") (pintype "passive"))
      (node (ref "U12") (pin "6") (pinfunction "-IN_B_6") (pintype "passive"))
    )
    (net (code "55") (name "Net-(U12C--IN_C)") (class "Default")
      (node (ref "C83") (pin "1") (pinfunction "1_1") (pintype "passive"))
      (node (ref "R43") (pin "2") (pinfunction "2_2") (pintype "passive"))
      (node (ref "R44") (pin "1") (pinfunction "1_1") (pintype "passive"))
      (node (ref "U12") (pin "9") (pinfunction "-IN_C_9") (pintype "passive"))
    )
    (net (code "56") (name "Net-(U12D--IN_D)") (class "Default")
      (node (ref "C86") (pin "1") (pinfunction "1_1") (pintype "passive"))
      (node (ref "R49") (pin "2") (pinfunction "2_2") (pintype "passive"))
      (node (ref "R50") (pin "1") (pinfunction "1_1") (pintype "passive"))
      (node (ref "U12") (pin "13") (pinfunction "-IN_D_13") (pintype "passive"))
    )
    (net (code "57") (name "Net-(U13-IN3)") (class "Default")
      (node (ref "R45") (pin "1") (pinfunction "1_1") (pintype "passive"))
      (node (ref "U13") (pin "3") (pinfunction "IN3_3") (pintype "passive"))
    )
    (net (code "58") (name "Net-(U13-IN4)") (class "Default")
      (node (ref "R46") (pin "1") (pinfunction "1_1") (pintype "passive"))
      (node (ref "U13") (pin "4") (pinfunction "IN4_4") (pintype "passive"))
    )
    (net (code "59") (name "Net-(U13-OUT1)") (class "Default")
      (node (ref "K5") (pin "8") (pinfunction "8_8") (pintype "passive"))
      (node (ref "U13") (pin "10") (pinfunction "OUT1_10") (pintype "passive"))
    )
    (net (code "60") (name "Net-(U13-OUT2)") (class "Default")
      (node (ref "K6") (pin "8") (pinfunction "8_8") (pintype "passive"))
      (node (ref "U13") (pin "9") (pinfunction "OUT2_9") (pintype "passive"))
    )
    (net (code "61") (name "unconnected-(K1-Pad2)") (class "Default")
      (node (ref "K1") (pin "2") (pinfunction "2_2") (pintype "passive+no_connect"))
    )
    (net (code "62") (name "unconnected-(K1-Pad7)") (class "Default")
      (node (ref "K1") (pin "7") (pinfunction "7_7") (pintype "passive+no_connect"))
    )
    (net (code "63") (name "unconnected-(K2-Pad2)") (class "Default")
      (node (ref "K2") (pin "2") (pinfunction "2_2") (pintype "passive+no_connect"))
    )
    (net (code "64") (name "unconnected-(K2-Pad7)") (class "Default")
      (node (ref "K2") (pin "7") (pinfunction "7_7") (pintype "passive+no_connect"))
    )
    (net (code "65") (name "unconnected-(K3-Pad2)") (class "Default")
      (node (ref "K3") (pin "2") (pinfunction "2_2") (pintype "passive+no_connect"))
    )
    (net (code "66") (name "unconnected-(K3-Pad7)") (class "Default")
      (node (ref "K3") (pin "7") (pinfunction "7_7") (pintype "passive+no_connect"))
    )
    (net (code "67") (name "unconnected-(K4-Pad2)") (class "Default")
      (node (ref "K4") (pin "2") (pinfunction "2_2") (pintype "passive+no_connect"))
    )
    (net (code "68") (name "unconnected-(K4-Pad7)") (class "Default")
      (node (ref "K4") (pin "7") (pinfunction "7_7") (pintype "passive+no_connect"))
    )
    (net (code "69") (name "unconnected-(K5-Pad2)") (class "Default")
      (node (ref "K5") (pin "2") (pinfunction "2_2") (pintype "passive+no_connect"))
    )
    (net (code "70") (name "unconnected-(K5-Pad7)") (class "Default")
      (node (ref "K5") (pin "7") (pinfunction "7_7") (pintype "passive+no_connect"))
    )
    (net (code "71") (name "unconnected-(K6-Pad2)") (class "Default")
      (node (ref "K6") (pin "2") (pinfunction "2_2") (pintype "passive+no_connect"))
    )
    (net (code "72") (name "unconnected-(K6-Pad7)") (class "Default")
      (node (ref "K6") (pin "7") (pinfunction "7_7") (pintype "passive+no_connect"))
    )
    (net (code "73") (name "unconnected-(U9-NC-Pad5)") (class "Default")
      (node (ref "U9") (pin "5") (pinfunction "NC_5") (pintype "passive+no_connect"))
    )
    (net (code "74") (name "unconnected-(U13-OUT3-Pad8)") (class "Default")
      (node (ref "U13") (pin "8") (pinfunction "OUT3_8") (pintype "passive+no_connect"))
    )
    (net (code "75") (name "unconnected-(U13-OUT4-Pad7)") (class "Default")
      (node (ref "U13") (pin "7") (pinfunction "OUT4_7") (pintype "passive+no_connect"))
    )
  )
)
